# PCB0M8B2.net
KiCad netlist of a schematic drawn in EAGLE
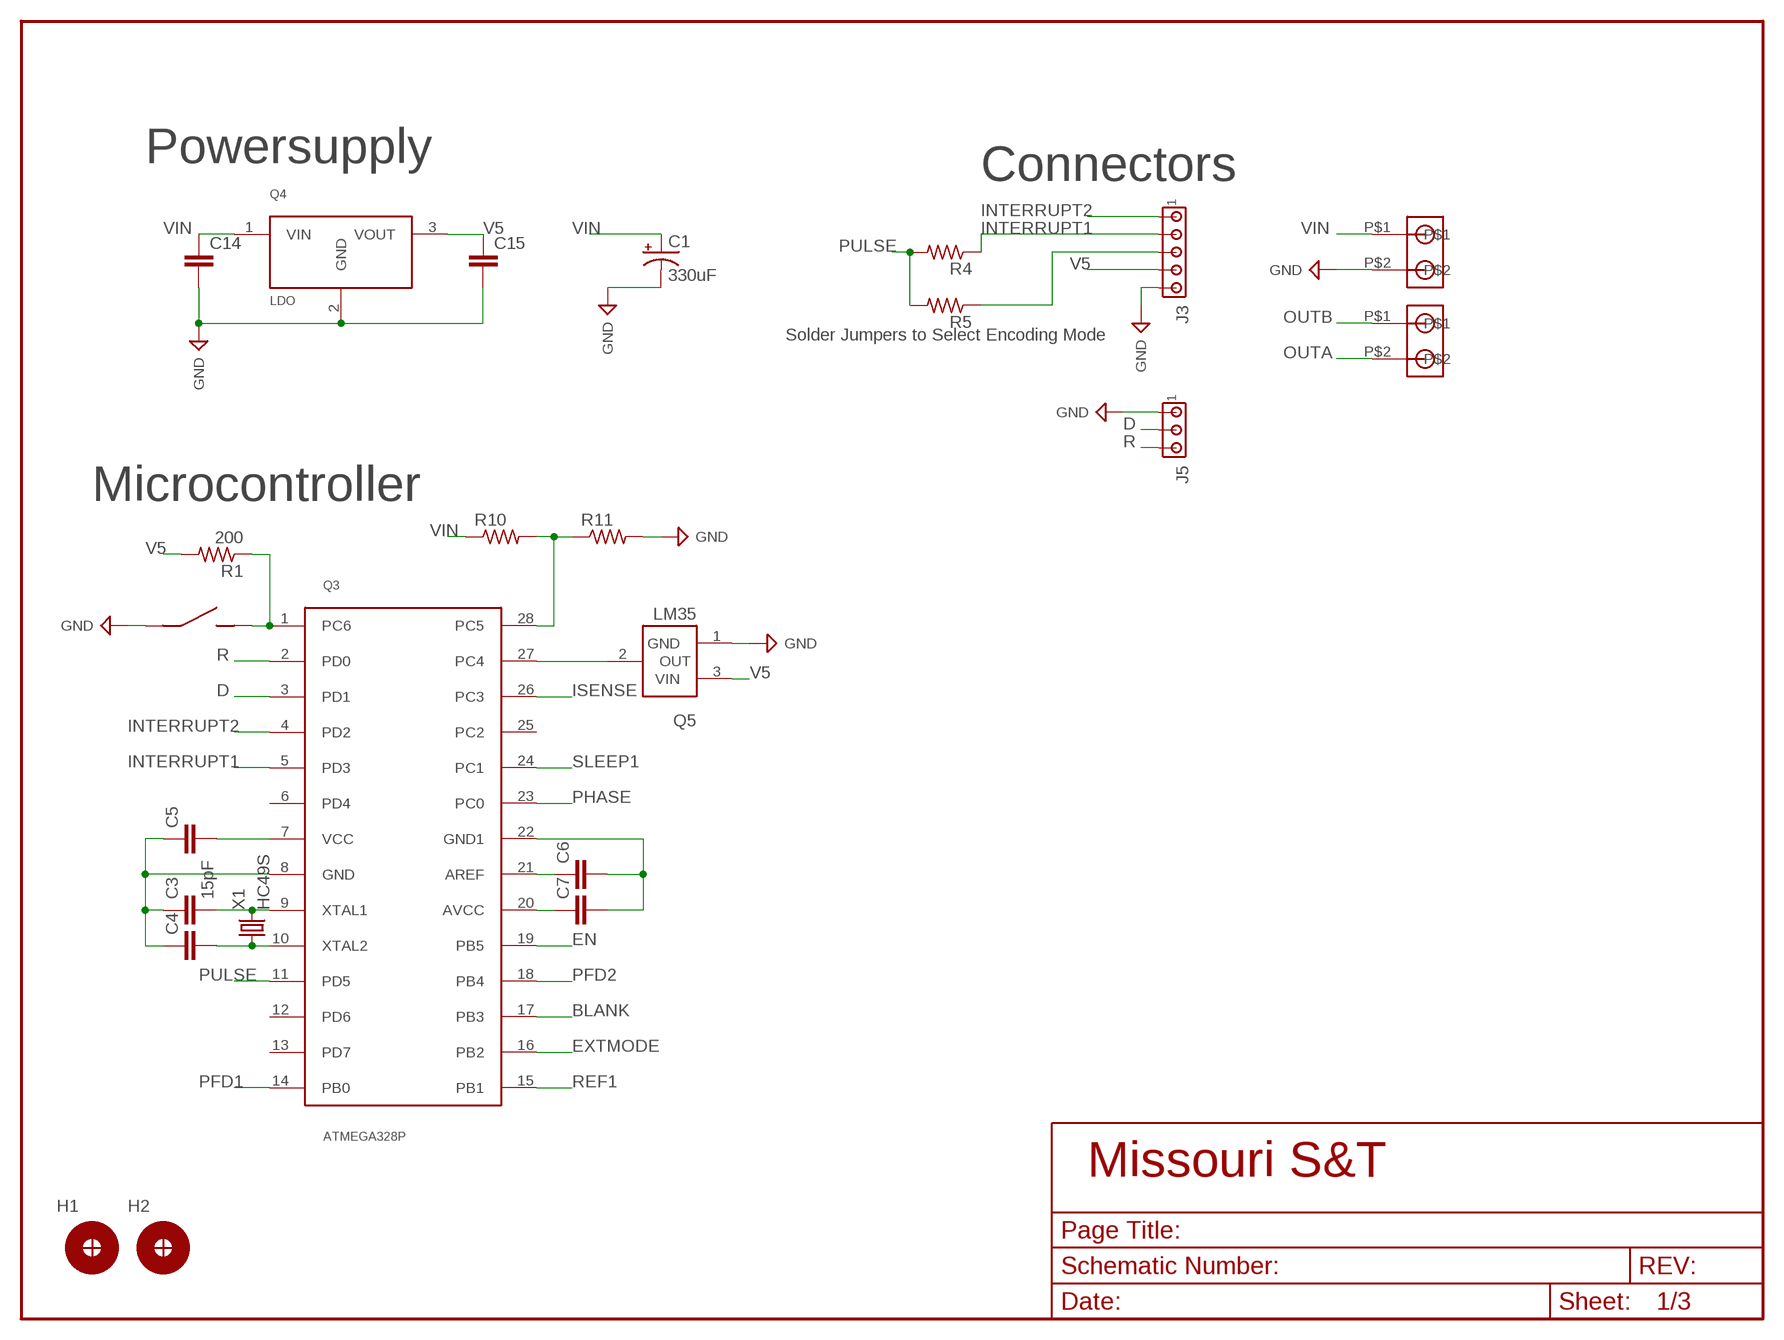
[diagram p0: schematic, sheet 1]
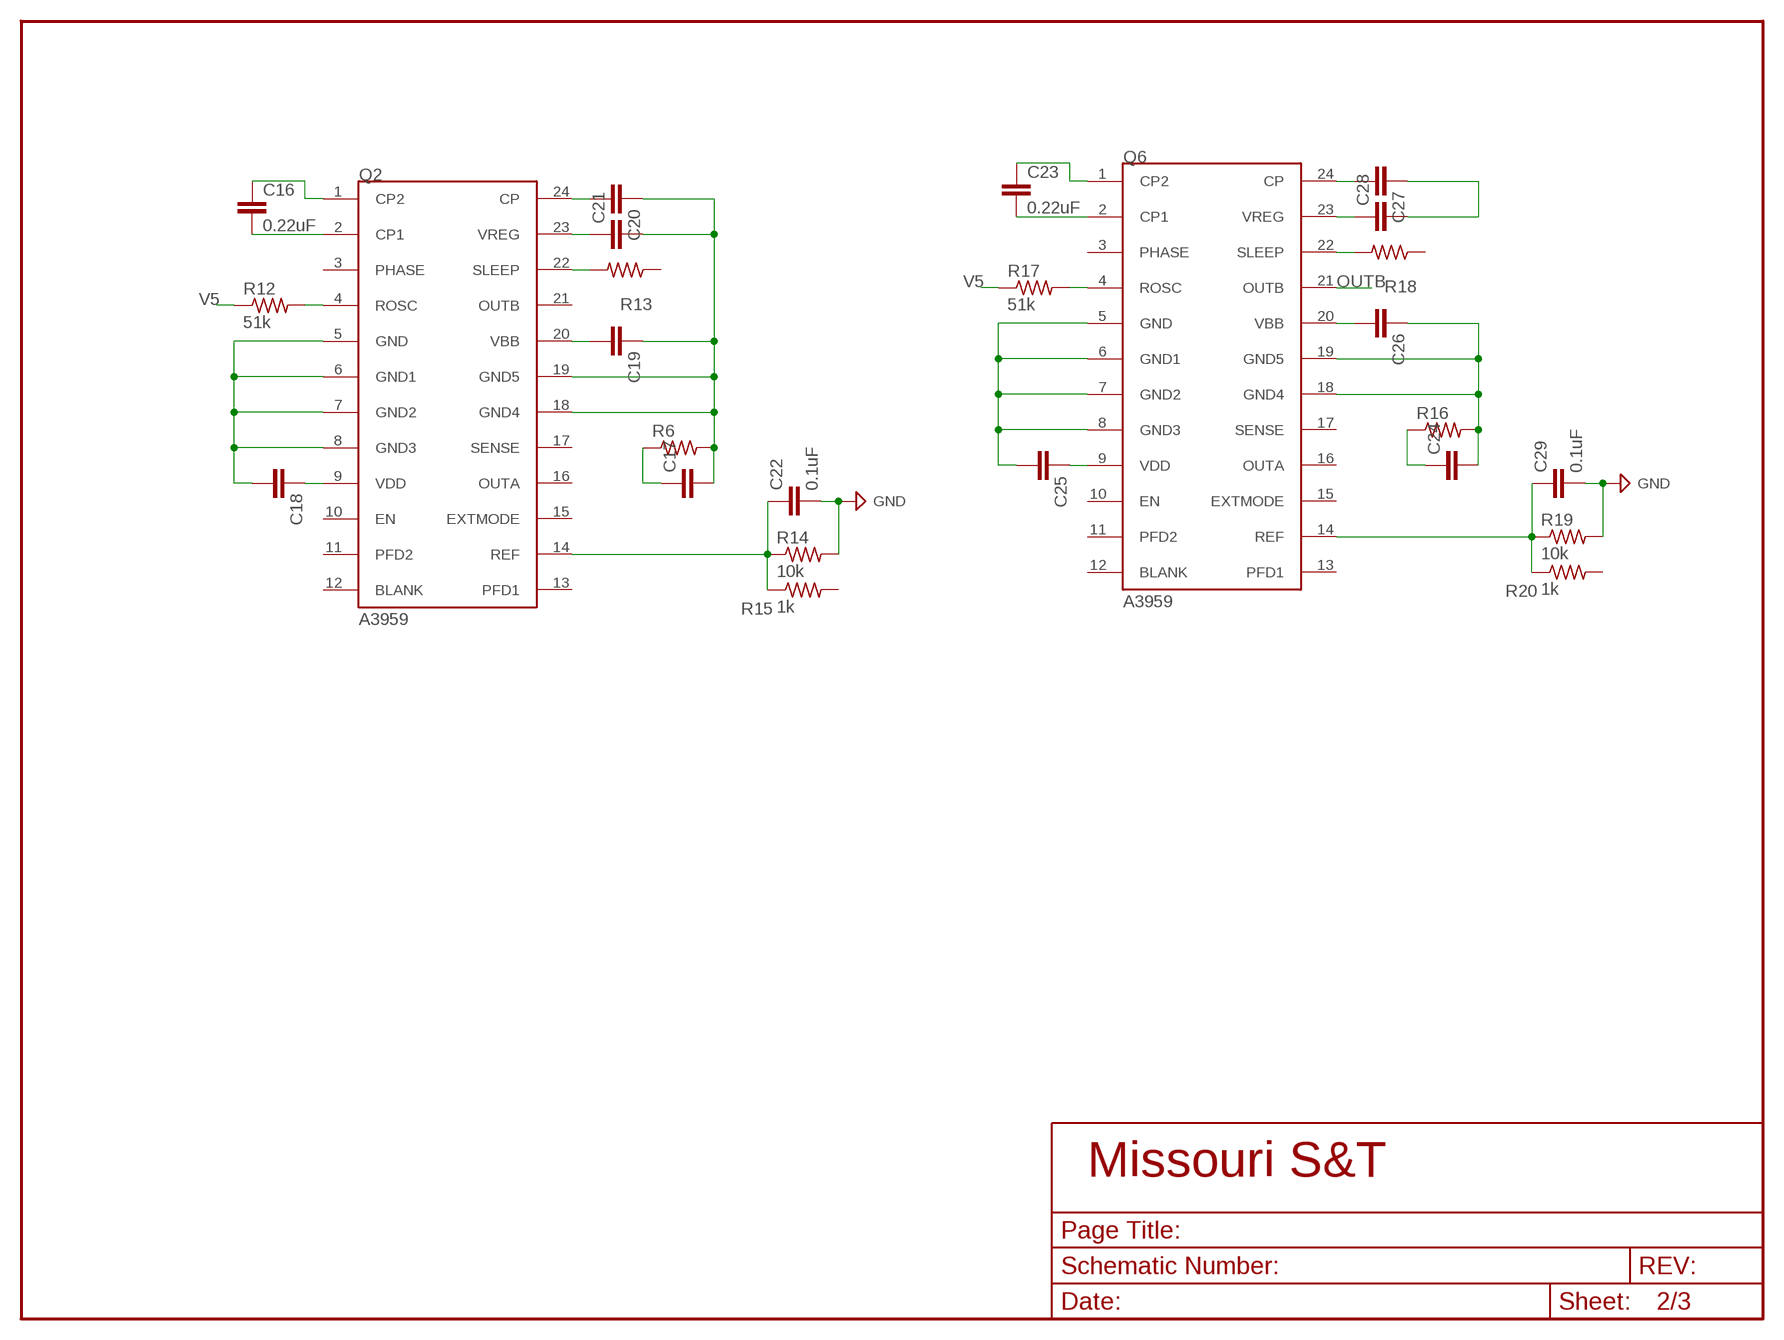
[diagram p1: schematic, sheet 2]
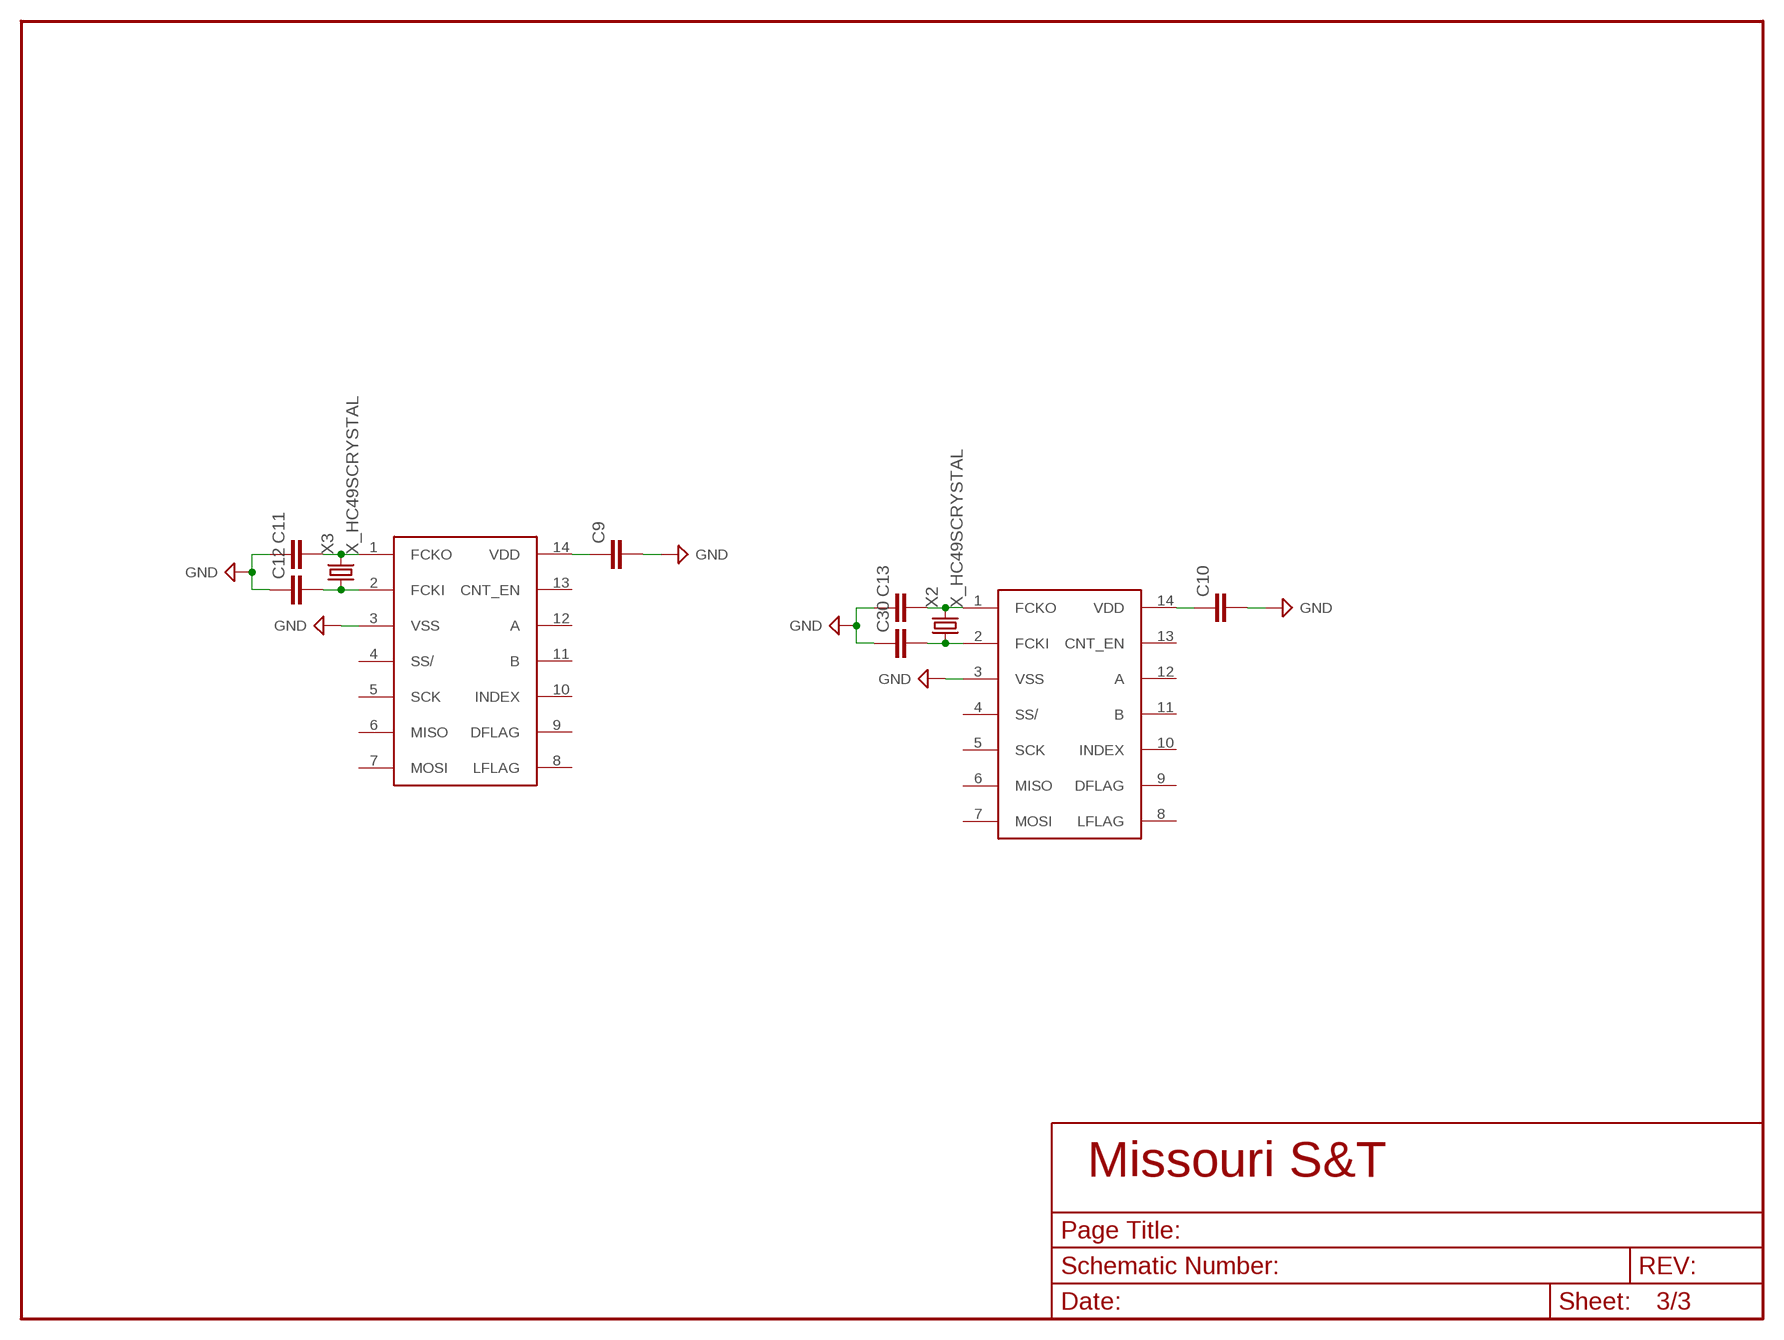
[diagram p2: schematic, sheet 3]

(export (version "E")
  (design (tool "Eeschema 10.0.6"))
  (components
    (comp (ref "C9")
      (value "C_CAP_1206")
      (footprint "eagle-import:C_1206")
      (libsource (lib "eagle-import") (part "C_CAP_1206"))
    )
    (comp (ref "C10")
      (value "C_CAP_0805")
      (footprint "eagle-import:C_0805")
      (libsource (lib "eagle-import") (part "C_CAP_0805"))
    )
    (comp (ref "C11")
      (value "C_CAP_0805")
      (footprint "eagle-import:C_0805")
      (libsource (lib "eagle-import") (part "C_CAP_0805"))
    )
    (comp (ref "C12")
      (value "C_CAP_0805")
      (footprint "eagle-import:C_0805")
      (libsource (lib "eagle-import") (part "C_CAP_0805"))
    )
    (comp (ref "C13")
      (value "C_CAP_0805")
      (footprint "eagle-import:C_0805")
      (libsource (lib "eagle-import") (part "C_CAP_0805"))
    )
    (comp (ref "C30")
      (value "C_CAP_0805")
      (footprint "eagle-import:C_0805")
      (libsource (lib "eagle-import") (part "C_CAP_0805"))
    )
    (comp (ref "Q8")
      (value "Q_LFLS7366R-S")
      (footprint "eagle-import:SOIC14")
      (libsource (lib "eagle-import") (part "Q_LFLS7366R-S"))
    )
    (comp (ref "Q9")
      (value "Q_LFLS7366R-S")
      (footprint "eagle-import:SOIC14")
      (libsource (lib "eagle-import") (part "Q_LFLS7366R-S"))
    )
    (comp (ref "X2")
      (value "X_HC49SCRYSTAL")
      (footprint "eagle-import:HC-49")
      (libsource (lib "eagle-import") (part "X_HC49SCRYSTAL"))
    )
    (comp (ref "X3")
      (value "X_HC49SCRYSTAL")
      (footprint "eagle-import:HC-49")
      (libsource (lib "eagle-import") (part "X_HC49SCRYSTAL"))
    )
    (comp (ref "C1")
      (value "330uF")
      (footprint "eagle-import:C_8MM")
      (libsource (lib "eagle-import") (part "C_POL8MM"))
    )
    (comp (ref "C3")
      (value "15pF")
      (footprint "eagle-import:C_0805")
      (libsource (lib "eagle-import") (part "C_CAP_0805"))
    )
    (comp (ref "C4")
      (value "C_CAP_0805")
      (footprint "eagle-import:C_0805")
      (libsource (lib "eagle-import") (part "C_CAP_0805"))
    )
    (comp (ref "C5")
      (value "C_CAP_0805")
      (footprint "eagle-import:C_0805")
      (libsource (lib "eagle-import") (part "C_CAP_0805"))
    )
    (comp (ref "C6")
      (value "C_CAP_0805")
      (footprint "eagle-import:C_0805")
      (libsource (lib "eagle-import") (part "C_CAP_0805"))
    )
    (comp (ref "C7")
      (value "C_CAP_0805")
      (footprint "eagle-import:C_0805")
      (libsource (lib "eagle-import") (part "C_CAP_0805"))
    )
    (comp (ref "C14")
      (value "C_CAP_0805")
      (footprint "eagle-import:C_0805")
      (libsource (lib "eagle-import") (part "C_CAP_0805"))
    )
    (comp (ref "C15")
      (value "C_CAP_0805")
      (footprint "eagle-import:C_0805")
      (libsource (lib "eagle-import") (part "C_CAP_0805"))
    )
    (comp (ref "H1")
      (value "H_MNTHOLE_#4")
      (footprint "eagle-import:H_MNTHOLE_#4")
      (libsource (lib "eagle-import") (part "H_MNTHOLE_#4"))
    )
    (comp (ref "H2")
      (value "H_MNTHOLE_#4")
      (footprint "eagle-import:H_MNTHOLE_#4")
      (libsource (lib "eagle-import") (part "H_MNTHOLE_#4"))
    )
    (comp (ref "J1")
      (value "J_1546074-2282834-2")
      (footprint "eagle-import:J_2.54MM")
      (libsource (lib "eagle-import") (part "J_1546074-2282834-2"))
    )
    (comp (ref "J2")
      (value "J_1546074-2282834-2")
      (footprint "eagle-import:J_2.54MM")
      (libsource (lib "eagle-import") (part "J_1546074-2282834-2"))
    )
    (comp (ref "J3")
      (value "J_MTA5P_100")
      (footprint "eagle-import:J_MTA100_5P")
      (libsource (lib "eagle-import") (part "J_MTA5P_100"))
    )
    (comp (ref "J4")
      (value "J_MC32857")
      (footprint "eagle-import:J_TOGGLE")
      (libsource (lib "eagle-import") (part "J_MC32857"))
    )
    (comp (ref "J5")
      (value "J_MTA3P_100")
      (footprint "eagle-import:J_MTA100_3P")
      (libsource (lib "eagle-import") (part "J_MTA3P_100"))
    )
    (comp (ref "Q3")
      (value "ATMEGA328P")
      (footprint "eagle-import:DIP28")
      (libsource (lib "eagle-import") (part "Q_ATMEGA328P"))
    )
    (comp (ref "Q4")
      (value "LDO")
      (footprint "eagle-import:TO-220")
      (libsource (lib "eagle-import") (part "Q_LDO"))
    )
    (comp (ref "Q5")
      (value "LM35")
      (footprint "eagle-import:TO-92-3")
      (libsource (lib "eagle-import") (part "Q_LM35"))
    )
    (comp (ref "R1")
      (value "200")
      (footprint "eagle-import:R_0805")
      (libsource (lib "eagle-import") (part "R_RES_0805"))
    )
    (comp (ref "R4")
      (value "R_RES_0603")
      (footprint "eagle-import:R_0603")
      (libsource (lib "eagle-import") (part "R_RES_0603"))
    )
    (comp (ref "R5")
      (value "R_RES_0603")
      (footprint "eagle-import:R_0603")
      (libsource (lib "eagle-import") (part "R_RES_0603"))
    )
    (comp (ref "R10")
      (value "R_RES_0805")
      (footprint "eagle-import:R_0805")
      (libsource (lib "eagle-import") (part "R_RES_0805"))
    )
    (comp (ref "R11")
      (value "R_RES_0805")
      (footprint "eagle-import:R_0805")
      (libsource (lib "eagle-import") (part "R_RES_0805"))
    )
    (comp (ref "X1")
      (value "HC49S")
      (footprint "eagle-import:HC-49")
      (libsource (lib "eagle-import") (part "X_HC49SCRYSTAL"))
    )
    (comp (ref "C16")
      (value "0.22uF")
      (footprint "eagle-import:C_0805")
      (libsource (lib "eagle-import") (part "C_CAP_0805"))
    )
    (comp (ref "C17")
      (value "C_CAP_0805")
      (footprint "eagle-import:C_0805")
      (libsource (lib "eagle-import") (part "C_CAP_0805"))
    )
    (comp (ref "C18")
      (value "C_CAP_0805")
      (footprint "eagle-import:C_0805")
      (libsource (lib "eagle-import") (part "C_CAP_0805"))
    )
    (comp (ref "C19")
      (value "C_CAP_0805")
      (footprint "eagle-import:C_0805")
      (libsource (lib "eagle-import") (part "C_CAP_0805"))
    )
    (comp (ref "C20")
      (value "C_CAP_0805")
      (footprint "eagle-import:C_0805")
      (libsource (lib "eagle-import") (part "C_CAP_0805"))
    )
    (comp (ref "C21")
      (value "C_CAP_0805")
      (footprint "eagle-import:C_0805")
      (libsource (lib "eagle-import") (part "C_CAP_0805"))
    )
    (comp (ref "C22")
      (value "0.1uF")
      (footprint "eagle-import:C_0805")
      (libsource (lib "eagle-import") (part "C_CAP_0805"))
    )
    (comp (ref "C23")
      (value "0.22uF")
      (footprint "eagle-import:C_0805")
      (libsource (lib "eagle-import") (part "C_CAP_0805"))
    )
    (comp (ref "C24")
      (value "C_CAP_0805")
      (footprint "eagle-import:C_0805")
      (libsource (lib "eagle-import") (part "C_CAP_0805"))
    )
    (comp (ref "C25")
      (value "C_CAP_0805")
      (footprint "eagle-import:C_0805")
      (libsource (lib "eagle-import") (part "C_CAP_0805"))
    )
    (comp (ref "C26")
      (value "C_CAP_0805")
      (footprint "eagle-import:C_0805")
      (libsource (lib "eagle-import") (part "C_CAP_0805"))
    )
    (comp (ref "C27")
      (value "C_CAP_0805")
      (footprint "eagle-import:C_0805")
      (libsource (lib "eagle-import") (part "C_CAP_0805"))
    )
    (comp (ref "C28")
      (value "C_CAP_0805")
      (footprint "eagle-import:C_0805")
      (libsource (lib "eagle-import") (part "C_CAP_0805"))
    )
    (comp (ref "C29")
      (value "0.1uF")
      (footprint "eagle-import:C_0805")
      (libsource (lib "eagle-import") (part "C_CAP_0805"))
    )
    (comp (ref "Q2")
      (value "A3959")
      (footprint "eagle-import:DIP24")
      (libsource (lib "eagle-import") (part "Q_A3959"))
    )
    (comp (ref "Q6")
      (value "A3959")
      (footprint "eagle-import:DIP24")
      (libsource (lib "eagle-import") (part "Q_A3959"))
    )
    (comp (ref "R6")
      (value "R_RES_2010")
      (footprint "eagle-import:R_2010")
      (libsource (lib "eagle-import") (part "R_RES_2010"))
    )
    (comp (ref "R12")
      (value "51k")
      (footprint "eagle-import:R_0805")
      (libsource (lib "eagle-import") (part "R_RES_0805"))
    )
    (comp (ref "R13")
      (value "R_1/4WL")
      (footprint "eagle-import:R_1_4WL")
      (libsource (lib "eagle-import") (part "R_1/4WL"))
    )
    (comp (ref "R14")
      (value "10k")
      (footprint "eagle-import:R_0805")
      (libsource (lib "eagle-import") (part "R_RES_0805"))
    )
    (comp (ref "R15")
      (value "1k")
      (footprint "eagle-import:R_0805")
      (libsource (lib "eagle-import") (part "R_RES_0805"))
    )
    (comp (ref "R16")
      (value "R_RES_2010")
      (footprint "eagle-import:R_2010")
      (libsource (lib "eagle-import") (part "R_RES_2010"))
    )
    (comp (ref "R17")
      (value "51k")
      (footprint "eagle-import:R_0805")
      (libsource (lib "eagle-import") (part "R_RES_0805"))
    )
    (comp (ref "R18")
      (value "R_1/4WL")
      (footprint "eagle-import:R_1_4WL")
      (libsource (lib "eagle-import") (part "R_1/4WL"))
    )
    (comp (ref "R19")
      (value "10k")
      (footprint "eagle-import:R_0805")
      (libsource (lib "eagle-import") (part "R_RES_0805"))
    )
    (comp (ref "R20")
      (value "1k")
      (footprint "eagle-import:R_0805")
      (libsource (lib "eagle-import") (part "R_RES_0805"))
    )
  )
  (nets
    (net (code "1") (name "BLANK") (class "Default")
      (node (ref "Q3") (pin "17") (pinfunction "PB3_17") (pintype "bidirectional"))
    )
    (net (code "2") (name "D") (class "Default")
      (node (ref "J5") (pin "2") (pinfunction "2_2") (pintype "passive"))
      (node (ref "Q3") (pin "3") (pinfunction "PD1_3") (pintype "bidirectional"))
    )
    (net (code "3") (name "EN") (class "Default")
      (node (ref "Q3") (pin "19") (pinfunction "PB5_19") (pintype "bidirectional"))
    )
    (net (code "4") (name "EXTMODE") (class "Default")
      (node (ref "Q3") (pin "16") (pinfunction "PB2_16") (pintype "bidirectional"))
    )
    (net (code "5") (name "GND") (class "Default")
      (node (ref "C1") (pin "-") (pinfunction "-_-") (pintype "passive"))
      (node (ref "C10") (pin "2") (pinfunction "2_2") (pintype "passive"))
      (node (ref "C11") (pin "1") (pinfunction "1_1") (pintype "passive"))
      (node (ref "C12") (pin "1") (pinfunction "1_1") (pintype "passive"))
      (node (ref "C13") (pin "1") (pinfunction "1_1") (pintype "passive"))
      (node (ref "C14") (pin "2") (pinfunction "2_2") (pintype "passive"))
      (node (ref "C15") (pin "2") (pinfunction "2_2") (pintype "passive"))
      (node (ref "C17") (pin "2") (pinfunction "2_2") (pintype "passive"))
      (node (ref "C18") (pin "2") (pinfunction "2_2") (pintype "passive"))
      (node (ref "C19") (pin "1") (pinfunction "1_1") (pintype "passive"))
      (node (ref "C20") (pin "1") (pinfunction "1_1") (pintype "passive"))
      (node (ref "C21") (pin "2") (pinfunction "2_2") (pintype "passive"))
      (node (ref "C22") (pin "2") (pinfunction "2_2") (pintype "passive"))
      (node (ref "C24") (pin "2") (pinfunction "2_2") (pintype "passive"))
      (node (ref "C25") (pin "2") (pinfunction "2_2") (pintype "passive"))
      (node (ref "C26") (pin "1") (pinfunction "1_1") (pintype "passive"))
      (node (ref "C29") (pin "2") (pinfunction "2_2") (pintype "passive"))
      (node (ref "C3") (pin "1") (pinfunction "1_1") (pintype "passive"))
      (node (ref "C30") (pin "1") (pinfunction "1_1") (pintype "passive"))
      (node (ref "C4") (pin "1") (pinfunction "1_1") (pintype "passive"))
      (node (ref "C5") (pin "1") (pinfunction "1_1") (pintype "passive"))
      (node (ref "C6") (pin "2") (pinfunction "2_2") (pintype "passive"))
      (node (ref "C7") (pin "2") (pinfunction "2_2") (pintype "passive"))
      (node (ref "C9") (pin "2") (pinfunction "2_2") (pintype "passive"))
      (node (ref "J1") (pin "P$2") (pinfunction "P$2_P$2") (pintype "bidirectional"))
      (node (ref "J3") (pin "5") (pinfunction "5_5") (pintype "passive"))
      (node (ref "J4") (pin "P$1") (pinfunction "1_P$1") (pintype "bidirectional"))
      (node (ref "J5") (pin "1") (pinfunction "1_1") (pintype "passive"))
      (node (ref "Q2") (pin "18") (pinfunction "GND4_18") (pintype "bidirectional"))
      (node (ref "Q2") (pin "19") (pinfunction "GND5_19") (pintype "bidirectional"))
      (node (ref "Q2") (pin "5") (pinfunction "GND_5") (pintype "bidirectional"))
      (node (ref "Q2") (pin "6") (pinfunction "GND1_6") (pintype "bidirectional"))
      (node (ref "Q2") (pin "7") (pinfunction "GND2_7") (pintype "bidirectional"))
      (node (ref "Q2") (pin "8") (pinfunction "GND3_8") (pintype "bidirectional"))
      (node (ref "Q3") (pin "22") (pinfunction "GND1_22") (pintype "bidirectional"))
      (node (ref "Q3") (pin "8") (pinfunction "GND_8") (pintype "bidirectional"))
      (node (ref "Q4") (pin "2") (pinfunction "GND_2") (pintype "bidirectional"))
      (node (ref "Q5") (pin "1") (pinfunction "GND_1") (pintype "bidirectional"))
      (node (ref "Q6") (pin "18") (pinfunction "GND4_18") (pintype "bidirectional"))
      (node (ref "Q6") (pin "19") (pinfunction "GND5_19") (pintype "bidirectional"))
      (node (ref "Q6") (pin "5") (pinfunction "GND_5") (pintype "bidirectional"))
      (node (ref "Q6") (pin "6") (pinfunction "GND1_6") (pintype "bidirectional"))
      (node (ref "Q6") (pin "7") (pinfunction "GND2_7") (pintype "bidirectional"))
      (node (ref "Q6") (pin "8") (pinfunction "GND3_8") (pintype "bidirectional"))
      (node (ref "Q8") (pin "3") (pinfunction "VSS_3") (pintype "bidirectional"))
      (node (ref "Q9") (pin "3") (pinfunction "VSS_3") (pintype "bidirectional"))
      (node (ref "R11") (pin "2") (pinfunction "2_2") (pintype "passive"))
      (node (ref "R14") (pin "2") (pinfunction "2_2") (pintype "passive"))
      (node (ref "R16") (pin "2") (pinfunction "2_2") (pintype "passive"))
      (node (ref "R19") (pin "2") (pinfunction "2_2") (pintype "passive"))
      (node (ref "R6") (pin "2") (pinfunction "2_2") (pintype "passive"))
    )
    (net (code "6") (name "INTERRUPT1") (class "Default")
      (node (ref "J3") (pin "2") (pinfunction "2_2") (pintype "passive"))
      (node (ref "Q3") (pin "5") (pinfunction "PD3_5") (pintype "bidirectional"))
      (node (ref "R4") (pin "1") (pinfunction "1_1") (pintype "passive"))
    )
    (net (code "7") (name "INTERRUPT2") (class "Default")
      (node (ref "J3") (pin "1") (pinfunction "1_1") (pintype "passive"))
      (node (ref "Q3") (pin "4") (pinfunction "PD2_4") (pintype "bidirectional"))
    )
    (net (code "8") (name "ISENSE") (class "Default")
      (node (ref "C17") (pin "1") (pinfunction "1_1") (pintype "passive"))
      (node (ref "C24") (pin "1") (pinfunction "1_1") (pintype "passive"))
      (node (ref "Q3") (pin "26") (pinfunction "PC3_26") (pintype "bidirectional"))
      (node (ref "R16") (pin "1") (pinfunction "1_1") (pintype "passive"))
      (node (ref "R6") (pin "1") (pinfunction "1_1") (pintype "passive"))
    )
    (net (code "9") (name "Net-(C27-Pad1)") (class "Default")
      (node (ref "C27") (pin "1") (pinfunction "1_1") (pintype "passive"))
      (node (ref "C28") (pin "2") (pinfunction "2_2") (pintype "passive"))
    )
    (net (code "10") (name "Net-(J3-Pad3)") (class "Default")
      (node (ref "J3") (pin "3") (pinfunction "3_3") (pintype "passive"))
      (node (ref "R5") (pin "1") (pinfunction "1_1") (pintype "passive"))
    )
    (net (code "11") (name "Net-(J4-2)") (class "Default")
      (node (ref "J4") (pin "P$2") (pinfunction "2_P$2") (pintype "bidirectional"))
      (node (ref "Q3") (pin "1") (pinfunction "PC6_1") (pintype "bidirectional"))
      (node (ref "R1") (pin "1") (pinfunction "1_1") (pintype "passive"))
    )
    (net (code "12") (name "Net-(Q2-CP)") (class "Default")
      (node (ref "C20") (pin "2") (pinfunction "2_2") (pintype "passive"))
      (node (ref "Q2") (pin "24") (pinfunction "CP_24") (pintype "bidirectional"))
    )
    (net (code "13") (name "Net-(Q2-CP1)") (class "Default")
      (node (ref "C16") (pin "2") (pinfunction "2_2") (pintype "passive"))
      (node (ref "Q2") (pin "2") (pinfunction "CP1_2") (pintype "bidirectional"))
    )
    (net (code "14") (name "Net-(Q2-CP2)") (class "Default")
      (node (ref "C16") (pin "1") (pinfunction "1_1") (pintype "passive"))
      (node (ref "Q2") (pin "1") (pinfunction "CP2_1") (pintype "bidirectional"))
    )
    (net (code "15") (name "Net-(Q2-REF)") (class "Default")
      (node (ref "C22") (pin "1") (pinfunction "1_1") (pintype "passive"))
      (node (ref "Q2") (pin "14") (pinfunction "REF_14") (pintype "bidirectional"))
      (node (ref "R14") (pin "1") (pinfunction "1_1") (pintype "passive"))
      (node (ref "R15") (pin "1") (pinfunction "1_1") (pintype "passive"))
    )
    (net (code "16") (name "Net-(Q2-ROSC)") (class "Default")
      (node (ref "Q2") (pin "4") (pinfunction "ROSC_4") (pintype "bidirectional"))
      (node (ref "R12") (pin "2") (pinfunction "2_2") (pintype "passive"))
    )
    (net (code "17") (name "Net-(Q2-SLEEP)") (class "Default")
      (node (ref "Q2") (pin "22") (pinfunction "SLEEP_22") (pintype "bidirectional"))
      (node (ref "R13") (pin "2") (pinfunction "2_2") (pintype "passive"))
    )
    (net (code "18") (name "Net-(Q2-VBB)") (class "Default")
      (node (ref "C19") (pin "2") (pinfunction "2_2") (pintype "passive"))
      (node (ref "Q2") (pin "20") (pinfunction "VBB_20") (pintype "bidirectional"))
    )
    (net (code "19") (name "Net-(Q2-VREG)") (class "Default")
      (node (ref "C21") (pin "1") (pinfunction "1_1") (pintype "passive"))
      (node (ref "Q2") (pin "23") (pinfunction "VREG_23") (pintype "bidirectional"))
    )
    (net (code "20") (name "Net-(Q3-AREF)") (class "Default")
      (node (ref "C6") (pin "1") (pinfunction "1_1") (pintype "passive"))
      (node (ref "Q3") (pin "21") (pinfunction "AREF_21") (pintype "bidirectional"))
    )
    (net (code "21") (name "Net-(Q3-PC4)") (class "Default")
      (node (ref "Q3") (pin "27") (pinfunction "PC4_27") (pintype "bidirectional"))
      (node (ref "Q5") (pin "2") (pinfunction "OUT_2") (pintype "bidirectional"))
    )
    (net (code "22") (name "Net-(Q3-PC5)") (class "Default")
      (node (ref "Q3") (pin "28") (pinfunction "PC5_28") (pintype "bidirectional"))
      (node (ref "R10") (pin "2") (pinfunction "2_2") (pintype "passive"))
      (node (ref "R11") (pin "1") (pinfunction "1_1") (pintype "passive"))
    )
    (net (code "23") (name "Net-(Q3-XTAL1)") (class "Default")
      (node (ref "C3") (pin "2") (pinfunction "2_2") (pintype "passive"))
      (node (ref "Q3") (pin "9") (pinfunction "XTAL1_9") (pintype "bidirectional"))
      (node (ref "X1") (pin "P$2") (pinfunction "2_P$2") (pintype "passive"))
    )
    (net (code "24") (name "Net-(Q3-XTAL2)") (class "Default")
      (node (ref "C4") (pin "2") (pinfunction "2_2") (pintype "passive"))
      (node (ref "Q3") (pin "10") (pinfunction "XTAL2_10") (pintype "bidirectional"))
      (node (ref "X1") (pin "P$1") (pinfunction "1_P$1") (pintype "passive"))
    )
    (net (code "25") (name "Net-(Q6-CP)") (class "Default")
      (node (ref "C27") (pin "2") (pinfunction "2_2") (pintype "passive"))
      (node (ref "Q6") (pin "24") (pinfunction "CP_24") (pintype "bidirectional"))
    )
    (net (code "26") (name "Net-(Q6-CP1)") (class "Default")
      (node (ref "C23") (pin "2") (pinfunction "2_2") (pintype "passive"))
      (node (ref "Q6") (pin "2") (pinfunction "CP1_2") (pintype "bidirectional"))
    )
    (net (code "27") (name "Net-(Q6-CP2)") (class "Default")
      (node (ref "C23") (pin "1") (pinfunction "1_1") (pintype "passive"))
      (node (ref "Q6") (pin "1") (pinfunction "CP2_1") (pintype "bidirectional"))
    )
    (net (code "28") (name "Net-(Q6-REF)") (class "Default")
      (node (ref "C29") (pin "1") (pinfunction "1_1") (pintype "passive"))
      (node (ref "Q6") (pin "14") (pinfunction "REF_14") (pintype "bidirectional"))
      (node (ref "R19") (pin "1") (pinfunction "1_1") (pintype "passive"))
      (node (ref "R20") (pin "1") (pinfunction "1_1") (pintype "passive"))
    )
    (net (code "29") (name "Net-(Q6-ROSC)") (class "Default")
      (node (ref "Q6") (pin "4") (pinfunction "ROSC_4") (pintype "bidirectional"))
      (node (ref "R17") (pin "2") (pinfunction "2_2") (pintype "passive"))
    )
    (net (code "30") (name "Net-(Q6-SLEEP)") (class "Default")
      (node (ref "Q6") (pin "22") (pinfunction "SLEEP_22") (pintype "bidirectional"))
      (node (ref "R18") (pin "2") (pinfunction "2_2") (pintype "passive"))
    )
    (net (code "31") (name "Net-(Q6-VBB)") (class "Default")
      (node (ref "C26") (pin "2") (pinfunction "2_2") (pintype "passive"))
      (node (ref "Q6") (pin "20") (pinfunction "VBB_20") (pintype "bidirectional"))
    )
    (net (code "32") (name "Net-(Q6-VREG)") (class "Default")
      (node (ref "C28") (pin "1") (pinfunction "1_1") (pintype "passive"))
      (node (ref "Q6") (pin "23") (pinfunction "VREG_23") (pintype "bidirectional"))
    )
    (net (code "33") (name "Net-(Q8-FCKI)") (class "Default")
      (node (ref "C12") (pin "2") (pinfunction "2_2") (pintype "passive"))
      (node (ref "Q8") (pin "2") (pinfunction "FCKI_2") (pintype "bidirectional"))
      (node (ref "X3") (pin "P$1") (pinfunction "1_P$1") (pintype "passive"))
    )
    (net (code "34") (name "Net-(Q8-FCKO)") (class "Default")
      (node (ref "C11") (pin "2") (pinfunction "2_2") (pintype "passive"))
      (node (ref "Q8") (pin "1") (pinfunction "FCKO_1") (pintype "bidirectional"))
      (node (ref "X3") (pin "P$2") (pinfunction "2_P$2") (pintype "passive"))
    )
    (net (code "35") (name "Net-(Q8-VDD)") (class "Default")
      (node (ref "C9") (pin "1") (pinfunction "1_1") (pintype "passive"))
      (node (ref "Q8") (pin "14") (pinfunction "VDD_14") (pintype "bidirectional"))
    )
    (net (code "36") (name "Net-(Q9-FCKI)") (class "Default")
      (node (ref "C30") (pin "2") (pinfunction "2_2") (pintype "passive"))
      (node (ref "Q9") (pin "2") (pinfunction "FCKI_2") (pintype "bidirectional"))
      (node (ref "X2") (pin "P$1") (pinfunction "1_P$1") (pintype "passive"))
    )
    (net (code "37") (name "Net-(Q9-FCKO)") (class "Default")
      (node (ref "C13") (pin "2") (pinfunction "2_2") (pintype "passive"))
      (node (ref "Q9") (pin "1") (pinfunction "FCKO_1") (pintype "bidirectional"))
      (node (ref "X2") (pin "P$2") (pinfunction "2_P$2") (pintype "passive"))
    )
    (net (code "38") (name "Net-(Q9-VDD)") (class "Default")
      (node (ref "C10") (pin "1") (pinfunction "1_1") (pintype "passive"))
      (node (ref "Q9") (pin "14") (pinfunction "VDD_14") (pintype "bidirectional"))
    )
    (net (code "39") (name "OUTA") (class "Default")
      (node (ref "J2") (pin "P$2") (pinfunction "P$2_P$2") (pintype "bidirectional"))
    )
    (net (code "40") (name "OUTB") (class "Default")
      (node (ref "J2") (pin "P$1") (pinfunction "P$1_P$1") (pintype "bidirectional"))
      (node (ref "Q6") (pin "21") (pinfunction "OUTB_21") (pintype "bidirectional"))
    )
    (net (code "41") (name "PFD1") (class "Default")
      (node (ref "Q3") (pin "14") (pinfunction "PB0_14") (pintype "bidirectional"))
    )
    (net (code "42") (name "PFD2") (class "Default")
      (node (ref "Q3") (pin "18") (pinfunction "PB4_18") (pintype "bidirectional"))
    )
    (net (code "43") (name "PHASE") (class "Default")
      (node (ref "Q3") (pin "23") (pinfunction "PC0_23") (pintype "bidirectional"))
    )
    (net (code "44") (name "PULSE") (class "Default")
      (node (ref "Q3") (pin "11") (pinfunction "PD5_11") (pintype "bidirectional"))
      (node (ref "R4") (pin "2") (pinfunction "2_2") (pintype "passive"))
      (node (ref "R5") (pin "2") (pinfunction "2_2") (pintype "passive"))
    )
    (net (code "45") (name "R") (class "Default")
      (node (ref "J5") (pin "3") (pinfunction "3_3") (pintype "passive"))
      (node (ref "Q3") (pin "2") (pinfunction "PD0_2") (pintype "bidirectional"))
    )
    (net (code "46") (name "REF1") (class "Default")
      (node (ref "Q3") (pin "15") (pinfunction "PB1_15") (pintype "bidirectional"))
    )
    (net (code "47") (name "SLEEP1") (class "Default")
      (node (ref "Q3") (pin "24") (pinfunction "PC1_24") (pintype "bidirectional"))
    )
    (net (code "48") (name "V5") (class "Default")
      (node (ref "C15") (pin "1") (pinfunction "1_1") (pintype "passive"))
      (node (ref "C18") (pin "1") (pinfunction "1_1") (pintype "passive"))
      (node (ref "C25") (pin "1") (pinfunction "1_1") (pintype "passive"))
      (node (ref "C5") (pin "2") (pinfunction "2_2") (pintype "passive"))
      (node (ref "C7") (pin "1") (pinfunction "1_1") (pintype "passive"))
      (node (ref "J3") (pin "4") (pinfunction "4_4") (pintype "passive"))
      (node (ref "Q2") (pin "9") (pinfunction "VDD_9") (pintype "bidirectional"))
      (node (ref "Q3") (pin "20") (pinfunction "AVCC_20") (pintype "bidirectional"))
      (node (ref "Q3") (pin "7") (pinfunction "VCC_7") (pintype "bidirectional"))
      (node (ref "Q4") (pin "3") (pinfunction "VOUT_3") (pintype "bidirectional"))
      (node (ref "Q5") (pin "3") (pinfunction "VIN_3") (pintype "bidirectional"))
      (node (ref "Q6") (pin "9") (pinfunction "VDD_9") (pintype "bidirectional"))
      (node (ref "R1") (pin "2") (pinfunction "2_2") (pintype "passive"))
      (node (ref "R12") (pin "1") (pinfunction "1_1") (pintype "passive"))
      (node (ref "R17") (pin "1") (pinfunction "1_1") (pintype "passive"))
    )
    (net (code "49") (name "VIN") (class "Default")
      (node (ref "C1") (pin "+") (pinfunction "+_+") (pintype "passive"))
      (node (ref "C14") (pin "1") (pinfunction "1_1") (pintype "passive"))
      (node (ref "J1") (pin "P$1") (pinfunction "P$1_P$1") (pintype "bidirectional"))
      (node (ref "Q4") (pin "1") (pinfunction "VIN_1") (pintype "bidirectional"))
      (node (ref "R10") (pin "1") (pinfunction "1_1") (pintype "passive"))
    )
    (net (code "50") (name "unconnected-(H1-Pad1)") (class "Default")
      (node (ref "H1") (pin "1") (pinfunction "1_1") (pintype "passive"))
    )
    (net (code "51") (name "unconnected-(H2-Pad1)") (class "Default")
      (node (ref "H2") (pin "1") (pinfunction "1_1") (pintype "passive"))
    )
    (net (code "52") (name "unconnected-(Q2-BLANK-Pad12)") (class "Default")
      (node (ref "Q2") (pin "12") (pinfunction "BLANK_12") (pintype "bidirectional"))
    )
    (net (code "53") (name "unconnected-(Q2-EN-Pad10)") (class "Default")
      (node (ref "Q2") (pin "10") (pinfunction "EN_10") (pintype "bidirectional"))
    )
    (net (code "54") (name "unconnected-(Q2-EXTMODE-Pad15)") (class "Default")
      (node (ref "Q2") (pin "15") (pinfunction "EXTMODE_15") (pintype "bidirectional"))
    )
    (net (code "55") (name "unconnected-(Q2-OUTA-Pad16)") (class "Default")
      (node (ref "Q2") (pin "16") (pinfunction "OUTA_16") (pintype "bidirectional"))
    )
    (net (code "56") (name "unconnected-(Q2-OUTB-Pad21)") (class "Default")
      (node (ref "Q2") (pin "21") (pinfunction "OUTB_21") (pintype "bidirectional"))
    )
    (net (code "57") (name "unconnected-(Q2-PFD1-Pad13)") (class "Default")
      (node (ref "Q2") (pin "13") (pinfunction "PFD1_13") (pintype "bidirectional"))
    )
    (net (code "58") (name "unconnected-(Q2-PFD2-Pad11)") (class "Default")
      (node (ref "Q2") (pin "11") (pinfunction "PFD2_11") (pintype "bidirectional"))
    )
    (net (code "59") (name "unconnected-(Q2-PHASE-Pad3)") (class "Default")
      (node (ref "Q2") (pin "3") (pinfunction "PHASE_3") (pintype "bidirectional"))
    )
    (net (code "60") (name "unconnected-(Q2-SENSE-Pad17)") (class "Default")
      (node (ref "Q2") (pin "17") (pinfunction "SENSE_17") (pintype "bidirectional"))
    )
    (net (code "61") (name "unconnected-(Q3-PC2-Pad25)") (class "Default")
      (node (ref "Q3") (pin "25") (pinfunction "PC2_25") (pintype "bidirectional"))
    )
    (net (code "62") (name "unconnected-(Q3-PD4-Pad6)") (class "Default")
      (node (ref "Q3") (pin "6") (pinfunction "PD4_6") (pintype "bidirectional"))
    )
    (net (code "63") (name "unconnected-(Q3-PD6-Pad12)") (class "Default")
      (node (ref "Q3") (pin "12") (pinfunction "PD6_12") (pintype "bidirectional"))
    )
    (net (code "64") (name "unconnected-(Q3-PD7-Pad13)") (class "Default")
      (node (ref "Q3") (pin "13") (pinfunction "PD7_13") (pintype "bidirectional"))
    )
    (net (code "65") (name "unconnected-(Q6-BLANK-Pad12)") (class "Default")
      (node (ref "Q6") (pin "12") (pinfunction "BLANK_12") (pintype "bidirectional"))
    )
    (net (code "66") (name "unconnected-(Q6-EN-Pad10)") (class "Default")
      (node (ref "Q6") (pin "10") (pinfunction "EN_10") (pintype "bidirectional"))
    )
    (net (code "67") (name "unconnected-(Q6-EXTMODE-Pad15)") (class "Default")
      (node (ref "Q6") (pin "15") (pinfunction "EXTMODE_15") (pintype "bidirectional"))
    )
    (net (code "68") (name "unconnected-(Q6-OUTA-Pad16)") (class "Default")
      (node (ref "Q6") (pin "16") (pinfunction "OUTA_16") (pintype "bidirectional"))
    )
    (net (code "69") (name "unconnected-(Q6-PFD1-Pad13)") (class "Default")
      (node (ref "Q6") (pin "13") (pinfunction "PFD1_13") (pintype "bidirectional"))
    )
    (net (code "70") (name "unconnected-(Q6-PFD2-Pad11)") (class "Default")
      (node (ref "Q6") (pin "11") (pinfunction "PFD2_11") (pintype "bidirectional"))
    )
    (net (code "71") (name "unconnected-(Q6-PHASE-Pad3)") (class "Default")
      (node (ref "Q6") (pin "3") (pinfunction "PHASE_3") (pintype "bidirectional"))
    )
    (net (code "72") (name "unconnected-(Q6-SENSE-Pad17)") (class "Default")
      (node (ref "Q6") (pin "17") (pinfunction "SENSE_17") (pintype "bidirectional"))
    )
    (net (code "73") (name "unconnected-(Q8-A-Pad12)") (class "Default")
      (node (ref "Q8") (pin "12") (pinfunction "A_12") (pintype "bidirectional"))
    )
    (net (code "74") (name "unconnected-(Q8-B-Pad11)") (class "Default")
      (node (ref "Q8") (pin "11") (pinfunction "B_11") (pintype "bidirectional"))
    )
    (net (code "75") (name "unconnected-(Q8-CNT_EN-Pad13)") (class "Default")
      (node (ref "Q8") (pin "13") (pinfunction "CNT_EN_13") (pintype "bidirectional"))
    )
    (net (code "76") (name "unconnected-(Q8-DFLAG-Pad9)") (class "Default")
      (node (ref "Q8") (pin "9") (pinfunction "DFLAG_9") (pintype "bidirectional"))
    )
    (net (code "77") (name "unconnected-(Q8-INDEX-Pad10)") (class "Default")
      (node (ref "Q8") (pin "10") (pinfunction "INDEX_10") (pintype "bidirectional"))
    )
    (net (code "78") (name "unconnected-(Q8-LFLAG-Pad8)") (class "Default")
      (node (ref "Q8") (pin "8") (pinfunction "LFLAG_8") (pintype "bidirectional"))
    )
    (net (code "79") (name "unconnected-(Q8-MISO-Pad6)") (class "Default")
      (node (ref "Q8") (pin "6") (pinfunction "MISO_6") (pintype "bidirectional"))
    )
    (net (code "80") (name "unconnected-(Q8-MOSI-Pad7)") (class "Default")
      (node (ref "Q8") (pin "7") (pinfunction "MOSI_7") (pintype "bidirectional"))
    )
    (net (code "81") (name "unconnected-(Q8-SCK-Pad5)") (class "Default")
      (node (ref "Q8") (pin "5") (pinfunction "SCK_5") (pintype "bidirectional"))
    )
    (net (code "82") (name "unconnected-(Q8-SS{slash}-Pad4)") (class "Default")
      (node (ref "Q8") (pin "4") (pinfunction "SS/_4") (pintype "bidirectional"))
    )
    (net (code "83") (name "unconnected-(Q9-A-Pad12)") (class "Default")
      (node (ref "Q9") (pin "12") (pinfunction "A_12") (pintype "bidirectional"))
    )
    (net (code "84") (name "unconnected-(Q9-B-Pad11)") (class "Default")
      (node (ref "Q9") (pin "11") (pinfunction "B_11") (pintype "bidirectional"))
    )
    (net (code "85") (name "unconnected-(Q9-CNT_EN-Pad13)") (class "Default")
      (node (ref "Q9") (pin "13") (pinfunction "CNT_EN_13") (pintype "bidirectional"))
    )
    (net (code "86") (name "unconnected-(Q9-DFLAG-Pad9)") (class "Default")
      (node (ref "Q9") (pin "9") (pinfunction "DFLAG_9") (pintype "bidirectional"))
    )
    (net (code "87") (name "unconnected-(Q9-INDEX-Pad10)") (class "Default")
      (node (ref "Q9") (pin "10") (pinfunction "INDEX_10") (pintype "bidirectional"))
    )
    (net (code "88") (name "unconnected-(Q9-LFLAG-Pad8)") (class "Default")
      (node (ref "Q9") (pin "8") (pinfunction "LFLAG_8") (pintype "bidirectional"))
    )
    (net (code "89") (name "unconnected-(Q9-MISO-Pad6)") (class "Default")
      (node (ref "Q9") (pin "6") (pinfunction "MISO_6") (pintype "bidirectional"))
    )
    (net (code "90") (name "unconnected-(Q9-MOSI-Pad7)") (class "Default")
      (node (ref "Q9") (pin "7") (pinfunction "MOSI_7") (pintype "bidirectional"))
    )
    (net (code "91") (name "unconnected-(Q9-SCK-Pad5)") (class "Default")
      (node (ref "Q9") (pin "5") (pinfunction "SCK_5") (pintype "bidirectional"))
    )
    (net (code "92") (name "unconnected-(Q9-SS{slash}-Pad4)") (class "Default")
      (node (ref "Q9") (pin "4") (pinfunction "SS/_4") (pintype "bidirectional"))
    )
    (net (code "93") (name "unconnected-(R13-Pad1)") (class "Default")
      (node (ref "R13") (pin "1") (pinfunction "1_1") (pintype "passive"))
    )
    (net (code "94") (name "unconnected-(R15-Pad2)") (class "Default")
      (node (ref "R15") (pin "2") (pinfunction "2_2") (pintype "passive"))
    )
    (net (code "95") (name "unconnected-(R18-Pad1)") (class "Default")
      (node (ref "R18") (pin "1") (pinfunction "1_1") (pintype "passive"))
    )
    (net (code "96") (name "unconnected-(R20-Pad2)") (class "Default")
      (node (ref "R20") (pin "2") (pinfunction "2_2") (pintype "passive"))
    )
  )
)
